# H_Bridge_Mosate.net
KiCad netlist of a schematic drawn in Altium Designer
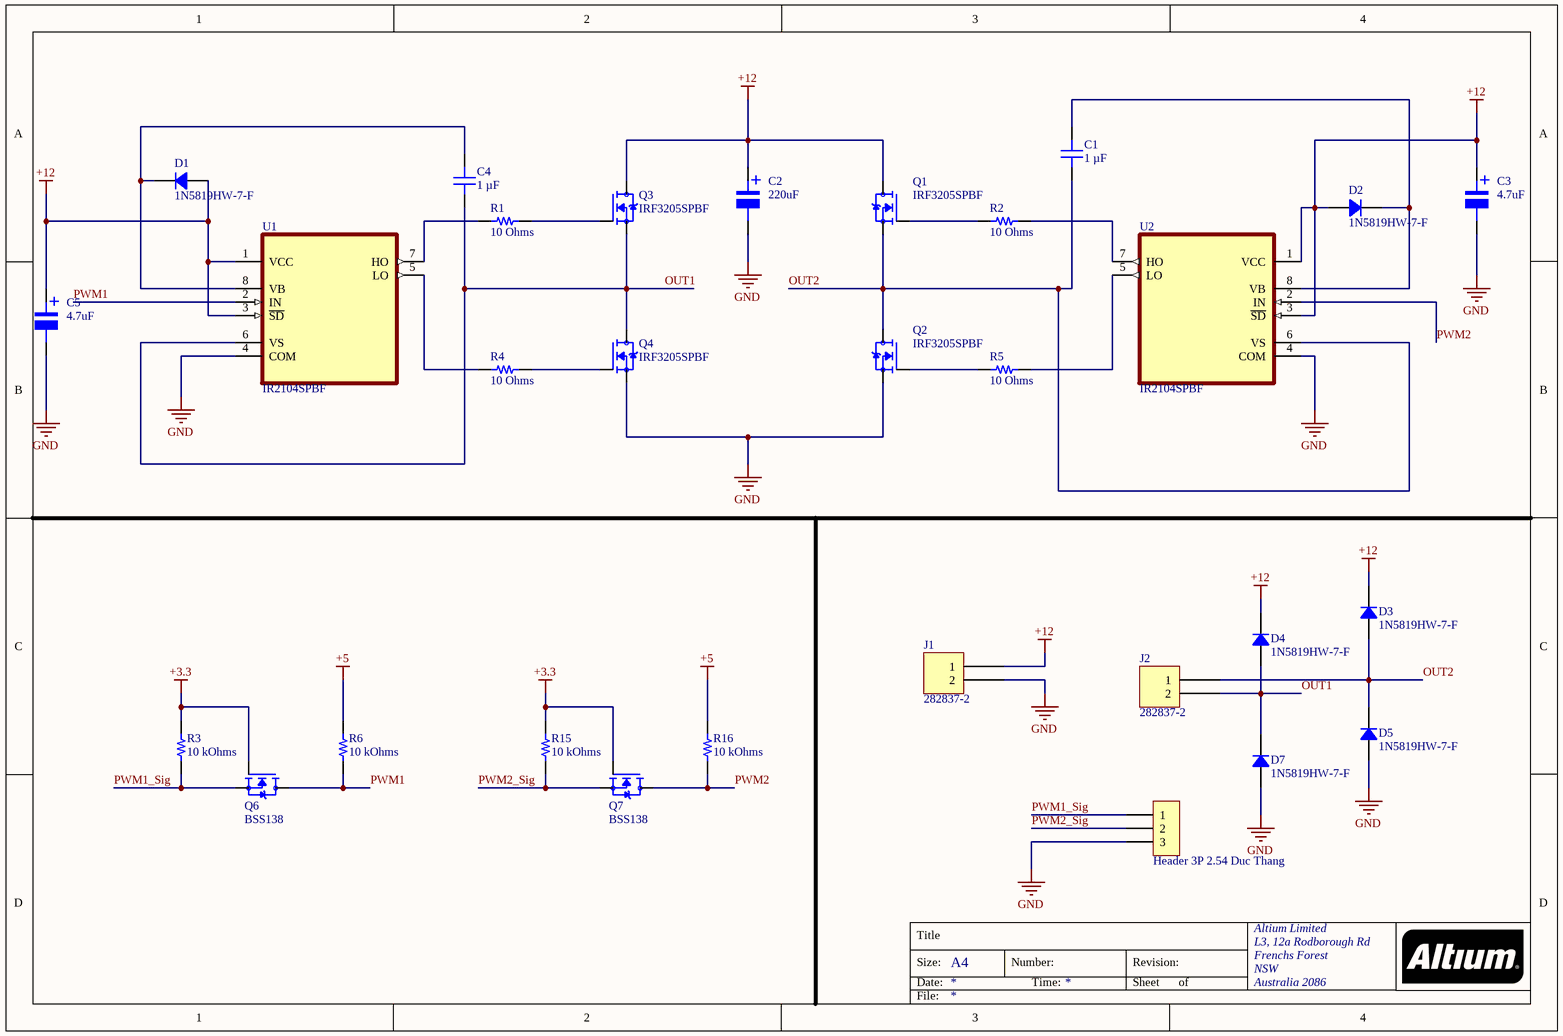
[diagram p0: H_Bridge_Mosate.SchDoc]

(export (version "E")
  (design (tool "Eeschema 10.0.6"))
  (components
    (comp (ref "C1")
      (value "1 µF")
      (footprint "CAP 0603_1608")
      (description "CAP CER 1UF 16V X8L 0603")
      (fields
        (field (name "PART NUMBER") "GCG188L8EE105KA07D")
        (field (name "MANUFACTURER") "Murata Electronics")
      )
      (libsource (lib "Celestial Altium Library - altium_library") (part "Capacitor"))
    )
    (comp (ref "C2")
      (value "220uF")
      (footprint "tu nhom 8 (f)")
      (description "Dán")
      (libsource (lib "Tu dien") (part "Tu Nhom 220uF 25V"))
    )
    (comp (ref "C3")
      (value "4.7uF")
      (footprint "tu nhom 4 (b)")
      (description "Dán")
      (libsource (lib "Tu dien") (part "Tu Nhom 4.7uF 25V"))
    )
    (comp (ref "C4")
      (value "1 µF")
      (footprint "CAP 0603_1608")
      (description "CAP CER 1UF 16V X8L 0603")
      (fields
        (field (name "PART NUMBER") "GCG188L8EE105KA07D")
        (field (name "MANUFACTURER") "Murata Electronics")
      )
      (libsource (lib "Celestial Altium Library - altium_library") (part "Capacitor"))
    )
    (comp (ref "C5")
      (value "4.7uF")
      (footprint "tu nhom 4 (b)")
      (description "Dán")
      (libsource (lib "Tu dien") (part "Tu Nhom 4.7uF 25V"))
    )
    (comp (ref "D1")
      (value "1N5819HW-7-F")
      (footprint "SOD-123")
      (description "DIODE SCHOTTKY 40V 1A SOD123")
      (fields (field (name "MANUFACTURER") "Diodes Incorporated"))
      (libsource (lib "Celestial Altium Library - altium_library") (part "Diode"))
    )
    (comp (ref "D2")
      (value "1N5819HW-7-F")
      (footprint "SOD-123")
      (description "DIODE SCHOTTKY 40V 1A SOD123")
      (fields (field (name "MANUFACTURER") "Diodes Incorporated"))
      (libsource (lib "Celestial Altium Library - altium_library") (part "Diode"))
    )
    (comp (ref "D3")
      (value "1N5819HW-7-F")
      (footprint "SOD-123")
      (description "DIODE SCHOTTKY 40V 1A SOD123")
      (fields (field (name "MANUFACTURER") "Diodes Incorporated"))
      (libsource (lib "Celestial Altium Library - altium_library") (part "Diode"))
    )
    (comp (ref "D4")
      (value "1N5819HW-7-F")
      (footprint "SOD-123")
      (description "DIODE SCHOTTKY 40V 1A SOD123")
      (fields (field (name "MANUFACTURER") "Diodes Incorporated"))
      (libsource (lib "Celestial Altium Library - altium_library") (part "Diode"))
    )
    (comp (ref "D5")
      (value "1N5819HW-7-F")
      (footprint "SOD-123")
      (description "DIODE SCHOTTKY 40V 1A SOD123")
      (fields (field (name "MANUFACTURER") "Diodes Incorporated"))
      (libsource (lib "Celestial Altium Library - altium_library") (part "Diode"))
    )
    (comp (ref "D7")
      (value "1N5819HW-7-F")
      (footprint "SOD-123")
      (description "DIODE SCHOTTKY 40V 1A SOD123")
      (fields (field (name "MANUFACTURER") "Diodes Incorporated"))
      (libsource (lib "Celestial Altium Library - altium_library") (part "Diode"))
    )
    (comp (ref "H1")
      (value "Header 3P 2.54 Duc Thang")
      (footprint "XH2.54M-3")
      (description "Cắm")
      (libsource (lib "Header") (part "Header 3P 2.54 Duc Thang"))
    )
    (comp (ref "J1")
      (value "282837-2")
      (footprint "TE 282837-2")
      (description "TERM BLK 2P SIDE ENT 5.08MM PCB")
      (fields (field (name "MANUFACTURER") "TE Connectivity AMP Connectors") (field (name "VOLTAGE") "300 V"))
      (libsource (lib "Celestial Altium Library - altium_library") (part "2 Pin"))
    )
    (comp (ref "J2")
      (value "282837-2")
      (footprint "TE 282837-2")
      (description "TERM BLK 2P SIDE ENT 5.08MM PCB")
      (fields (field (name "MANUFACTURER") "TE Connectivity AMP Connectors") (field (name "VOLTAGE") "300 V"))
      (libsource (lib "Celestial Altium Library - altium_library") (part "2 Pin"))
    )
    (comp (ref "Q1")
      (value "IRF3205SPBF")
      (footprint "TRANS_IRF3205SPBF")
      (fields (field (name "MF") "Infineon Technologies"))
      (libsource (lib "IRF3205SPBF") (part "IRF3205SPBF"))
    )
    (comp (ref "Q2")
      (value "IRF3205SPBF")
      (footprint "TRANS_IRF3205SPBF")
      (fields (field (name "MF") "Infineon Technologies"))
      (libsource (lib "IRF3205SPBF") (part "IRF3205SPBF"))
    )
    (comp (ref "Q3")
      (value "IRF3205SPBF")
      (footprint "TRANS_IRF3205SPBF")
      (fields (field (name "MF") "Infineon Technologies"))
      (libsource (lib "IRF3205SPBF") (part "IRF3205SPBF"))
    )
    (comp (ref "Q4")
      (value "IRF3205SPBF")
      (footprint "TRANS_IRF3205SPBF")
      (fields (field (name "MF") "Infineon Technologies"))
      (libsource (lib "IRF3205SPBF") (part "IRF3205SPBF"))
    )
    (comp (ref "Q6")
      (value "BSS138")
      (footprint "SOT95P240X111-3N")
      (description "N-Channel 50 V 220mA (Ta) 350mW (Ta) Surface Mount SOT-23-3")
      (fields (field (name "MF") "onsemi"))
      (libsource (lib "BSS138") (part "BSS138"))
    )
    (comp (ref "Q7")
      (value "BSS138")
      (footprint "SOT95P240X111-3N")
      (description "N-Channel 50 V 220mA (Ta) 350mW (Ta) Surface Mount SOT-23-3")
      (fields (field (name "MF") "onsemi"))
      (libsource (lib "BSS138") (part "BSS138"))
    )
    (comp (ref "R1")
      (value "10 Ohms")
      (footprint "RES 0603_1608")
      (description "RES 10 OHM 1% 1/4W 0603")
      (fields
        (field (name "PART NUMBER") "ERJ-UP3F10R0V")
        (field (name "MANUFACTURER") "Panasonic Electronic Components")
      )
      (libsource (lib "Celestial Altium Library - altium_library") (part "Resistor"))
    )
    (comp (ref "R2")
      (value "10 Ohms")
      (footprint "RES 0603_1608")
      (description "RES 10 OHM 1% 1/4W 0603")
      (fields
        (field (name "PART NUMBER") "ERJ-UP3F10R0V")
        (field (name "MANUFACTURER") "Panasonic Electronic Components")
      )
      (libsource (lib "Celestial Altium Library - altium_library") (part "Resistor"))
    )
    (comp (ref "R3")
      (value "10 kOhms")
      (footprint "RES 0603_1608")
      (description "RES SMD 10K OHM 1% 1/10W 0603")
      (fields (field (name "PART NUMBER") "AC0603FR-0710KL") (field (name "MANUFACTURER") "Yageo"))
      (libsource (lib "Celestial Altium Library - altium_library") (part "Resistor"))
    )
    (comp (ref "R4")
      (value "10 Ohms")
      (footprint "RES 0603_1608")
      (description "RES 10 OHM 1% 1/4W 0603")
      (fields
        (field (name "PART NUMBER") "ERJ-UP3F10R0V")
        (field (name "MANUFACTURER") "Panasonic Electronic Components")
      )
      (libsource (lib "Celestial Altium Library - altium_library") (part "Resistor"))
    )
    (comp (ref "R5")
      (value "10 Ohms")
      (footprint "RES 0603_1608")
      (description "RES 10 OHM 1% 1/4W 0603")
      (fields
        (field (name "PART NUMBER") "ERJ-UP3F10R0V")
        (field (name "MANUFACTURER") "Panasonic Electronic Components")
      )
      (libsource (lib "Celestial Altium Library - altium_library") (part "Resistor"))
    )
    (comp (ref "R6")
      (value "10 kOhms")
      (footprint "RES 0603_1608")
      (description "RES SMD 10K OHM 1% 1/10W 0603")
      (fields (field (name "PART NUMBER") "AC0603FR-0710KL") (field (name "MANUFACTURER") "Yageo"))
      (libsource (lib "Celestial Altium Library - altium_library") (part "Resistor"))
    )
    (comp (ref "R15")
      (value "10 kOhms")
      (footprint "RES 0603_1608")
      (description "RES SMD 10K OHM 1% 1/10W 0603")
      (fields (field (name "PART NUMBER") "AC0603FR-0710KL") (field (name "MANUFACTURER") "Yageo"))
      (libsource (lib "Celestial Altium Library - altium_library") (part "Resistor"))
    )
    (comp (ref "R16")
      (value "10 kOhms")
      (footprint "RES 0603_1608")
      (description "RES SMD 10K OHM 1% 1/10W 0603")
      (fields (field (name "PART NUMBER") "AC0603FR-0710KL") (field (name "MANUFACTURER") "Yageo"))
      (libsource (lib "Celestial Altium Library - altium_library") (part "Resistor"))
    )
    (comp (ref "U1")
      (value "IR2104SPBF")
      (footprint "SOIC127P600X175-8N")
      (fields (field (name "MF") "Infineon"))
      (libsource (lib "IR2104SPBF") (part "IR2104SPBF"))
    )
    (comp (ref "U2")
      (value "IR2104SPBF")
      (footprint "SOIC127P600X175-8N")
      (fields (field (name "MF") "Infineon"))
      (libsource (lib "") (part "IR2104SPBF_1"))
    )
  )
  (nets
    (net (code "1") (name "+3.3") (class "Default")
      (node (ref "Q6") (pin "1") (pinfunction "G_1") (pintype "passive"))
      (node (ref "Q7") (pin "1") (pinfunction "G_1") (pintype "passive"))
      (node (ref "R15") (pin "2") (pinfunction "2_2") (pintype "passive"))
      (node (ref "R3") (pin "2") (pinfunction "2_2") (pintype "passive"))
    )
    (net (code "2") (name "+5") (class "Default")
      (node (ref "R16") (pin "2") (pinfunction "2_2") (pintype "passive"))
      (node (ref "R6") (pin "2") (pinfunction "2_2") (pintype "passive"))
    )
    (net (code "3") (name "+12") (class "Default")
      (node (ref "C2") (pin "1") (pinfunction "1_1") (pintype "passive"))
      (node (ref "C3") (pin "1") (pinfunction "1_1") (pintype "passive"))
      (node (ref "C5") (pin "1") (pinfunction "1_1") (pintype "passive"))
      (node (ref "D1") (pin "1") (pinfunction "1_1") (pintype "passive"))
      (node (ref "D2") (pin "1") (pinfunction "1_1") (pintype "passive"))
      (node (ref "D3") (pin "2") (pinfunction "2_2") (pintype "passive"))
      (node (ref "D4") (pin "2") (pinfunction "2_2") (pintype "passive"))
      (node (ref "J1") (pin "1") (pinfunction "1_1") (pintype "passive"))
      (node (ref "Q1") (pin "2") (pinfunction "D_2") (pintype "passive"))
      (node (ref "Q3") (pin "2") (pinfunction "D_2") (pintype "passive"))
      (node (ref "U1") (pin "1") (pinfunction "VCC_1") (pintype "power_in"))
      (node (ref "U1") (pin "3") (pinfunction "~{SD}_3") (pintype "input"))
      (node (ref "U2") (pin "1") (pinfunction "VCC_1") (pintype "power_in"))
      (node (ref "U2") (pin "3") (pinfunction "~{SD}_3") (pintype "input"))
    )
    (net (code "4") (name "/OUT1") (class "Default")
      (node (ref "C4") (pin "1") (pinfunction "1_1") (pintype "passive"))
      (node (ref "D4") (pin "1") (pinfunction "1_1") (pintype "passive"))
      (node (ref "D7") (pin "2") (pinfunction "2_2") (pintype "passive"))
      (node (ref "J2") (pin "2") (pinfunction "2_2") (pintype "passive"))
      (node (ref "Q3") (pin "3") (pinfunction "S_3") (pintype "passive"))
      (node (ref "Q4") (pin "2") (pinfunction "D_2") (pintype "passive"))
      (node (ref "U1") (pin "6") (pinfunction "VS_6") (pintype "power_in"))
    )
    (net (code "5") (name "/OUT2") (class "Default")
      (node (ref "C1") (pin "1") (pinfunction "1_1") (pintype "passive"))
      (node (ref "D3") (pin "1") (pinfunction "1_1") (pintype "passive"))
      (node (ref "D5") (pin "2") (pinfunction "2_2") (pintype "passive"))
      (node (ref "J2") (pin "1") (pinfunction "1_1") (pintype "passive"))
      (node (ref "Q1") (pin "3") (pinfunction "S_3") (pintype "passive"))
      (node (ref "Q2") (pin "2") (pinfunction "D_2") (pintype "passive"))
      (node (ref "U2") (pin "6") (pinfunction "VS_6") (pintype "power_in"))
    )
    (net (code "6") (name "/PWM1") (class "Default")
      (node (ref "Q6") (pin "3") (pinfunction "D_3") (pintype "passive"))
      (node (ref "R6") (pin "1") (pinfunction "1_1") (pintype "passive"))
      (node (ref "U1") (pin "2") (pinfunction "IN_2") (pintype "input"))
    )
    (net (code "7") (name "/PWM1_Sig") (class "Default")
      (node (ref "H1") (pin "1") (pinfunction "1_1") (pintype "passive"))
      (node (ref "Q6") (pin "2") (pinfunction "S_2") (pintype "passive"))
      (node (ref "R3") (pin "1") (pinfunction "1_1") (pintype "passive"))
    )
    (net (code "8") (name "/PWM2") (class "Default")
      (node (ref "Q7") (pin "3") (pinfunction "D_3") (pintype "passive"))
      (node (ref "R16") (pin "1") (pinfunction "1_1") (pintype "passive"))
      (node (ref "U2") (pin "2") (pinfunction "IN_2") (pintype "input"))
    )
    (net (code "9") (name "/PWM2_Sig") (class "Default")
      (node (ref "H1") (pin "2") (pinfunction "2_2") (pintype "passive"))
      (node (ref "Q7") (pin "2") (pinfunction "S_2") (pintype "passive"))
      (node (ref "R15") (pin "1") (pinfunction "1_1") (pintype "passive"))
    )
    (net (code "10") (name "GND") (class "Default")
      (node (ref "C2") (pin "2") (pinfunction "2_2") (pintype "passive"))
      (node (ref "C3") (pin "2") (pinfunction "2_2") (pintype "passive"))
      (node (ref "C5") (pin "2") (pinfunction "2_2") (pintype "passive"))
      (node (ref "D5") (pin "1") (pinfunction "1_1") (pintype "passive"))
      (node (ref "D7") (pin "1") (pinfunction "1_1") (pintype "passive"))
      (node (ref "H1") (pin "3") (pinfunction "3_3") (pintype "passive"))
      (node (ref "J1") (pin "2") (pinfunction "2_2") (pintype "passive"))
      (node (ref "Q2") (pin "3") (pinfunction "S_3") (pintype "passive"))
      (node (ref "Q4") (pin "3") (pinfunction "S_3") (pintype "passive"))
      (node (ref "U1") (pin "4") (pinfunction "COM_4") (pintype "passive"))
      (node (ref "U2") (pin "4") (pinfunction "COM_4") (pintype "passive"))
    )
    (net (code "11") (name "Net-(Q1-G)") (class "Default")
      (node (ref "Q1") (pin "1") (pinfunction "G_1") (pintype "passive"))
      (node (ref "R2") (pin "1") (pinfunction "1_1") (pintype "passive"))
    )
    (net (code "12") (name "Net-(Q2-G)") (class "Default")
      (node (ref "Q2") (pin "1") (pinfunction "G_1") (pintype "passive"))
      (node (ref "R5") (pin "1") (pinfunction "1_1") (pintype "passive"))
    )
    (net (code "13") (name "Net-(Q3-G)") (class "Default")
      (node (ref "Q3") (pin "1") (pinfunction "G_1") (pintype "passive"))
      (node (ref "R1") (pin "2") (pinfunction "2_2") (pintype "passive"))
    )
    (net (code "14") (name "Net-(Q4-G)") (class "Default")
      (node (ref "Q4") (pin "1") (pinfunction "G_1") (pintype "passive"))
      (node (ref "R4") (pin "2") (pinfunction "2_2") (pintype "passive"))
    )
    (net (code "15") (name "Net-(U1-HO)") (class "Default")
      (node (ref "R1") (pin "1") (pinfunction "1_1") (pintype "passive"))
      (node (ref "U1") (pin "7") (pinfunction "HO_7") (pintype "output"))
    )
    (net (code "16") (name "Net-(U1-LO)") (class "Default")
      (node (ref "R4") (pin "1") (pinfunction "1_1") (pintype "passive"))
      (node (ref "U1") (pin "5") (pinfunction "LO_5") (pintype "output"))
    )
    (net (code "17") (name "Net-(U1-VB)") (class "Default")
      (node (ref "C4") (pin "2") (pinfunction "2_2") (pintype "passive"))
      (node (ref "D1") (pin "2") (pinfunction "2_2") (pintype "passive"))
      (node (ref "U1") (pin "8") (pinfunction "VB_8") (pintype "power_in"))
    )
    (net (code "18") (name "Net-(U2-HO)") (class "Default")
      (node (ref "R2") (pin "2") (pinfunction "2_2") (pintype "passive"))
      (node (ref "U2") (pin "7") (pinfunction "HO_7") (pintype "output"))
    )
    (net (code "19") (name "Net-(U2-LO)") (class "Default")
      (node (ref "R5") (pin "2") (pinfunction "2_2") (pintype "passive"))
      (node (ref "U2") (pin "5") (pinfunction "LO_5") (pintype "output"))
    )
    (net (code "20") (name "Net-(U2-VB)") (class "Default")
      (node (ref "C1") (pin "2") (pinfunction "2_2") (pintype "passive"))
      (node (ref "D2") (pin "2") (pinfunction "2_2") (pintype "passive"))
      (node (ref "U2") (pin "8") (pinfunction "VB_8") (pintype "power_in"))
    )
  )
)
